# ACS_sch.net
KiCad netlist of a schematic drawn in Altium Designer
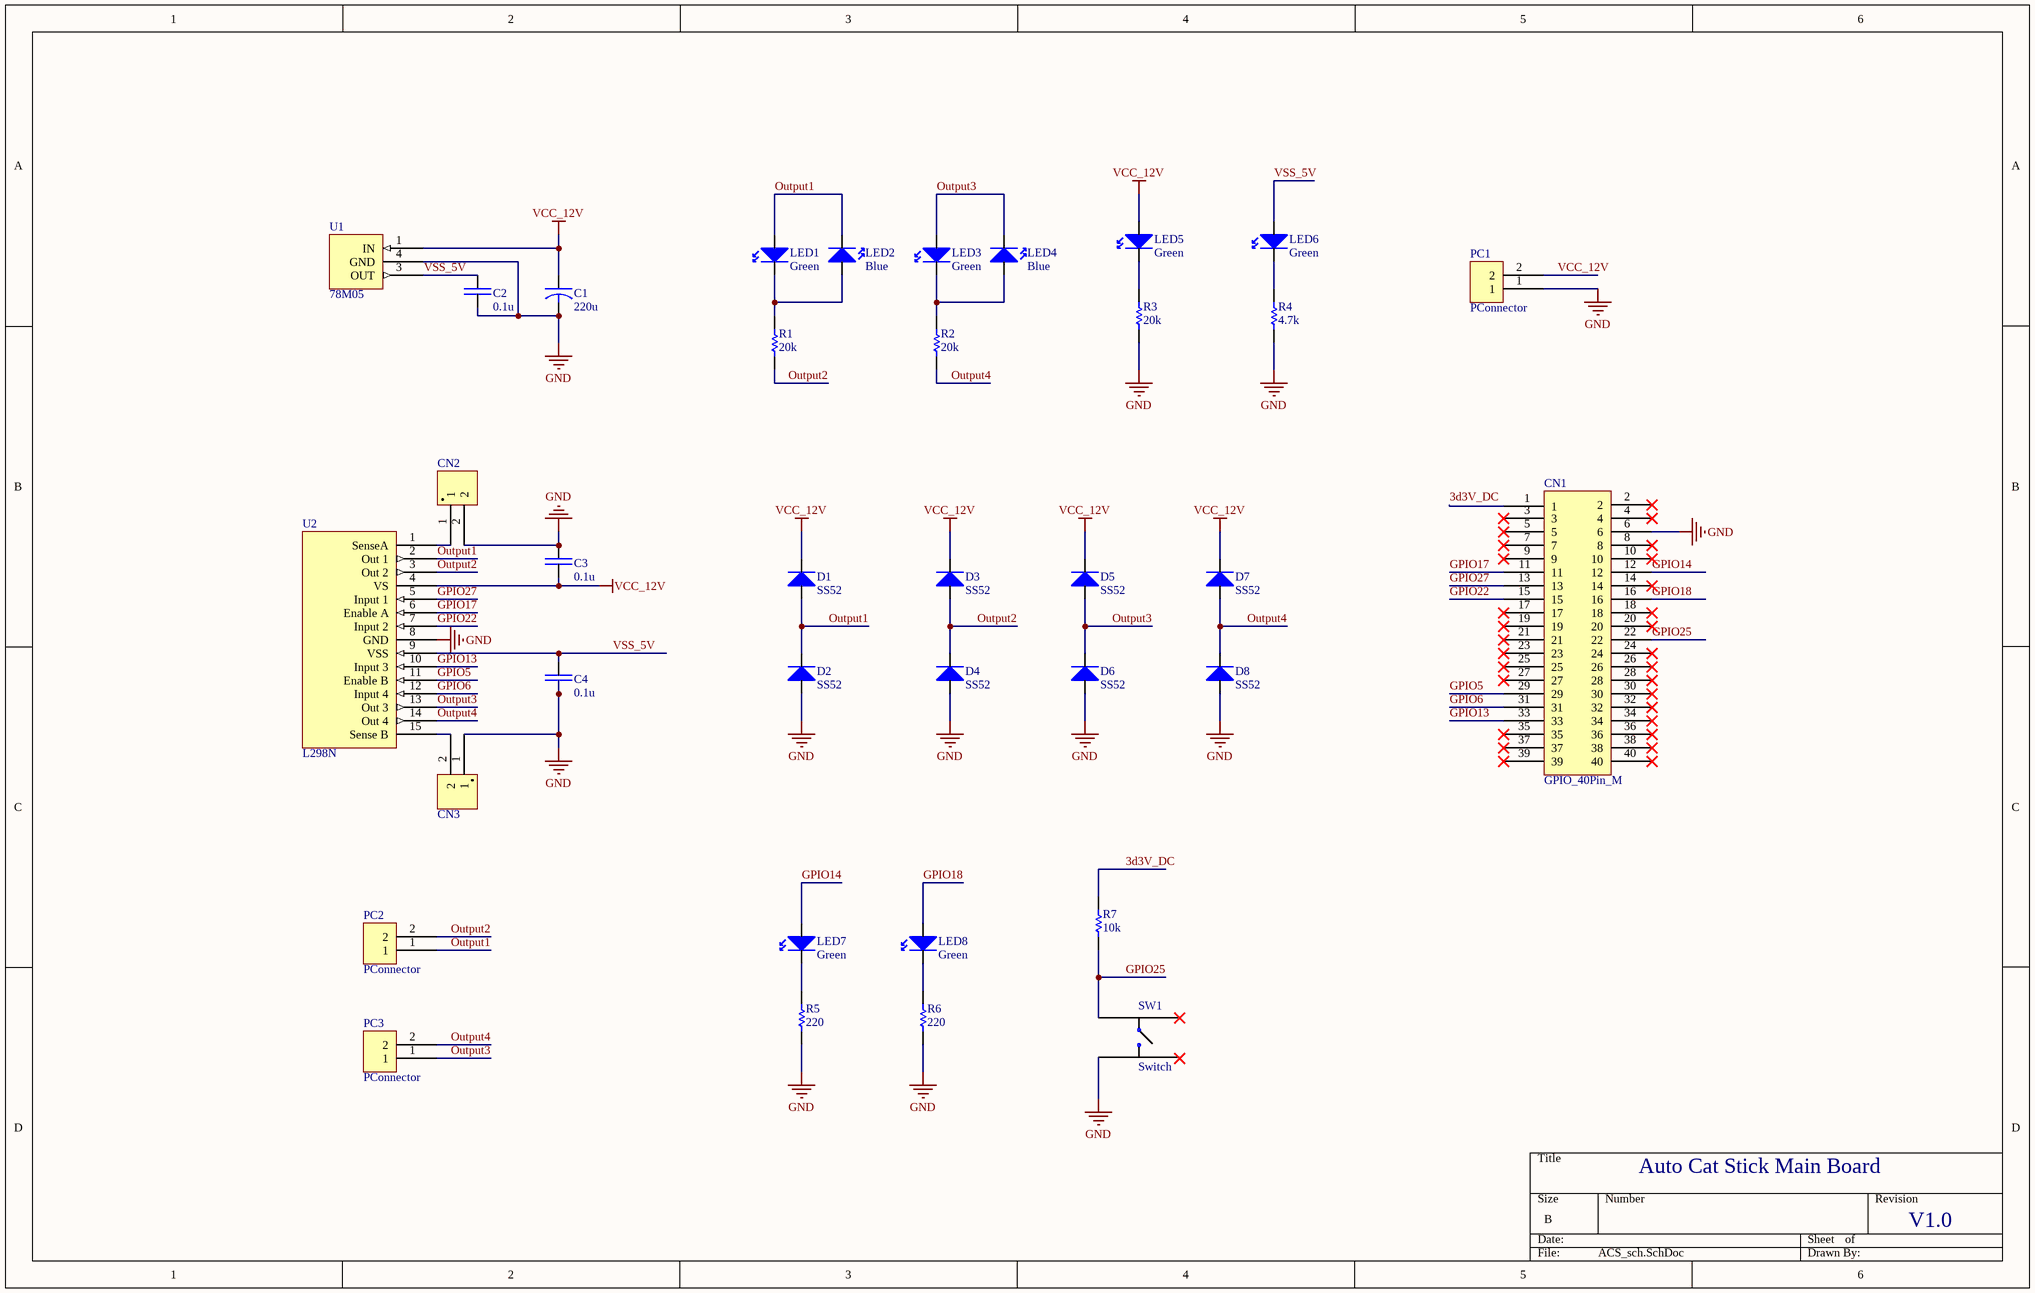
[diagram p0: ACS_sch.SchDoc]

(export (version "E")
  (design (tool "Eeschema 10.0.6"))
  (components
    (comp (ref "C1")
      (value "220u")
      (footprint "C0605")
      (description "C0605 Electrolytic Capacitor")
      (libsource (lib "ACS_SchLib") (part "cap 0605"))
    )
    (comp (ref "C2")
      (value "0.1u")
      (footprint "C0603")
      (description "C0603 non Electrolytic Capacitor")
      (libsource (lib "ACS_SchLib") (part "cap 0603 NonE"))
    )
    (comp (ref "C3")
      (value "0.1u")
      (footprint "C0603")
      (description "C0603 non Electrolytic Capacitor")
      (libsource (lib "ACS_SchLib") (part "cap 0603 NonE"))
    )
    (comp (ref "C4")
      (value "0.1u")
      (footprint "C0603")
      (description "C0603 non Electrolytic Capacitor")
      (libsource (lib "ACS_SchLib") (part "cap 0603 NonE"))
    )
    (comp (ref "CN1")
      (value "GPIO_40Pin_M")
      (footprint "GPIO_40Pin_M")
      (description "GPIO 40pin Male Connector")
      (libsource (lib "ACS_SchLib") (part "GPIO_40Pin_M"))
    )
    (comp (ref "CN2")
      (value "Connector")
      (footprint "2PIN")
      (description "2pin connector")
      (libsource (lib "ACS_SchLib") (part "Connector"))
    )
    (comp (ref "CN3")
      (value "Connector")
      (footprint "2PIN")
      (description "2pin connector")
      (libsource (lib "") (part "Connector_1"))
    )
    (comp (ref "D1")
      (value "SS52")
      (footprint "SMC(DO-214AB)")
      (description "SS52 Diode")
      (libsource (lib "ACS_SchLib") (part "SS52"))
    )
    (comp (ref "D2")
      (value "SS52")
      (footprint "SMC(DO-214AB)")
      (description "SS52 Diode")
      (libsource (lib "ACS_SchLib") (part "SS52"))
    )
    (comp (ref "D3")
      (value "SS52")
      (footprint "SMC(DO-214AB)")
      (description "SS52 Diode")
      (libsource (lib "ACS_SchLib") (part "SS52"))
    )
    (comp (ref "D4")
      (value "SS52")
      (footprint "SMC(DO-214AB)")
      (description "SS52 Diode")
      (libsource (lib "ACS_SchLib") (part "SS52"))
    )
    (comp (ref "D5")
      (value "SS52")
      (footprint "SMC(DO-214AB)")
      (description "SS52 Diode")
      (libsource (lib "ACS_SchLib") (part "SS52"))
    )
    (comp (ref "D6")
      (value "SS52")
      (footprint "SMC(DO-214AB)")
      (description "SS52 Diode")
      (libsource (lib "ACS_SchLib") (part "SS52"))
    )
    (comp (ref "D7")
      (value "SS52")
      (footprint "SMC(DO-214AB)")
      (description "SS52 Diode")
      (libsource (lib "ACS_SchLib") (part "SS52"))
    )
    (comp (ref "D8")
      (value "SS52")
      (footprint "SMC(DO-214AB)")
      (description "SS52 Diode")
      (libsource (lib "ACS_SchLib") (part "SS52"))
    )
    (comp (ref "LED1")
      (value "Green")
      (footprint "LED0603")
      (description "LED0603")
      (libsource (lib "ACS_SchLib") (part "led 0603"))
    )
    (comp (ref "LED2")
      (value "Blue")
      (footprint "LED0603")
      (description "LED0603")
      (libsource (lib "ACS_SchLib") (part "led 0603"))
    )
    (comp (ref "LED3")
      (value "Green")
      (footprint "LED0603")
      (description "LED0603")
      (libsource (lib "ACS_SchLib") (part "led 0603"))
    )
    (comp (ref "LED4")
      (value "Blue")
      (footprint "LED0603")
      (description "LED0603")
      (libsource (lib "ACS_SchLib") (part "led 0603"))
    )
    (comp (ref "LED5")
      (value "Green")
      (footprint "LED0603")
      (description "LED0603")
      (libsource (lib "ACS_SchLib") (part "led 0603"))
    )
    (comp (ref "LED6")
      (value "Green")
      (footprint "LED0603")
      (description "LED0603")
      (libsource (lib "ACS_SchLib") (part "led 0603"))
    )
    (comp (ref "LED7")
      (value "Green")
      (footprint "LED0603")
      (description "LED0603")
      (libsource (lib "ACS_SchLib") (part "led 0603"))
    )
    (comp (ref "LED8")
      (value "Green")
      (footprint "LED0603")
      (description "LED0603")
      (libsource (lib "ACS_SchLib") (part "led 0603"))
    )
    (comp (ref "PC1")
      (value "PConnector")
      (footprint "PC_2Pin")
      (description "2Pin")
      (libsource (lib "ACS_SchLib") (part "PConnector"))
    )
    (comp (ref "PC2")
      (value "PConnector")
      (footprint "PC_2Pin")
      (description "2Pin")
      (libsource (lib "ACS_SchLib") (part "PConnector"))
    )
    (comp (ref "PC3")
      (value "PConnector")
      (footprint "PC_2Pin")
      (description "2Pin")
      (libsource (lib "ACS_SchLib") (part "PConnector"))
    )
    (comp (ref "R1")
      (value "20k")
      (footprint "R0603")
      (description "Resistor")
      (libsource (lib "ACS_SchLib") (part "Res 0603"))
    )
    (comp (ref "R2")
      (value "20k")
      (footprint "R0603")
      (description "Resistor")
      (libsource (lib "ACS_SchLib") (part "Res 0603"))
    )
    (comp (ref "R3")
      (value "20k")
      (footprint "R0603")
      (description "Resistor")
      (libsource (lib "ACS_SchLib") (part "Res 0603"))
    )
    (comp (ref "R4")
      (value "4.7k")
      (footprint "R0603")
      (description "Resistor")
      (libsource (lib "ACS_SchLib") (part "Res 0603"))
    )
    (comp (ref "R5")
      (value "220")
      (footprint "R0603")
      (description "Resistor")
      (libsource (lib "ACS_SchLib") (part "Res 0603"))
    )
    (comp (ref "R6")
      (value "220")
      (footprint "R0603")
      (description "Resistor")
      (libsource (lib "ACS_SchLib") (part "Res 0603"))
    )
    (comp (ref "R7")
      (value "10k")
      (footprint "R0603")
      (description "Resistor")
      (libsource (lib "ACS_SchLib") (part "Res 0603"))
    )
    (comp (ref "SW1") (value "Switch") (footprint "Switch") (libsource (lib "ACS_SchLib") (part "Switch")))
    (comp (ref "U1")
      (value "78M05")
      (footprint "78M05")
      (description "Linear Voltage Regulators (LDO)")
      (libsource (lib "ACS_SchLib") (part "78M05"))
    )
    (comp (ref "U2")
      (value "L298N")
      (footprint "L298N")
      (description "HGSEMI L298N")
      (libsource (lib "ACS_SchLib") (part "L298N"))
    )
  )
  (nets
    (net (code "1") (name "/3d3V_DC") (class "Default")
      (node (ref "CN1") (pin "1") (pinfunction "1_1") (pintype "passive"))
      (node (ref "R7") (pin "2") (pinfunction "2_2") (pintype "passive"))
    )
    (net (code "3") (name "/GPIO5") (class "Default")
      (node (ref "CN1") (pin "29") (pinfunction "29_29") (pintype "passive"))
      (node (ref "U2") (pin "11") (pinfunction "Enable_B_11") (pintype "input"))
    )
    (net (code "4") (name "/GPIO6") (class "Default")
      (node (ref "CN1") (pin "31") (pinfunction "31_31") (pintype "passive"))
      (node (ref "U2") (pin "12") (pinfunction "Input_4_12") (pintype "input"))
    )
    (net (code "5") (name "/GPIO13") (class "Default")
      (node (ref "CN1") (pin "33") (pinfunction "33_33") (pintype "passive"))
      (node (ref "U2") (pin "10") (pinfunction "Input_3_10") (pintype "input"))
    )
    (net (code "6") (name "/GPIO14") (class "Default")
      (node (ref "CN1") (pin "12") (pinfunction "12_12") (pintype "passive"))
      (node (ref "LED7") (pin "2") (pinfunction "2_2") (pintype "passive"))
    )
    (net (code "7") (name "/GPIO17") (class "Default")
      (node (ref "CN1") (pin "11") (pinfunction "11_11") (pintype "passive"))
      (node (ref "U2") (pin "6") (pinfunction "Enable_A_6") (pintype "input"))
    )
    (net (code "8") (name "/GPIO18") (class "Default")
      (node (ref "CN1") (pin "16") (pinfunction "16_16") (pintype "passive"))
      (node (ref "LED8") (pin "2") (pinfunction "2_2") (pintype "passive"))
    )
    (net (code "9") (name "/GPIO22") (class "Default")
      (node (ref "CN1") (pin "15") (pinfunction "15_15") (pintype "passive"))
      (node (ref "U2") (pin "7") (pinfunction "Input_2_7") (pintype "input"))
    )
    (net (code "10") (name "/GPIO25") (class "Default")
      (node (ref "CN1") (pin "22") (pinfunction "22_22") (pintype "passive"))
      (node (ref "R7") (pin "1") (pinfunction "1_1") (pintype "passive"))
      (node (ref "SW1") (pin "1") (pinfunction "1_1") (pintype "passive"))
    )
    (net (code "11") (name "/GPIO27") (class "Default")
      (node (ref "CN1") (pin "13") (pinfunction "13_13") (pintype "passive"))
      (node (ref "U2") (pin "5") (pinfunction "Input_1_5") (pintype "input"))
    )
    (net (code "12") (name "/Output1") (class "Default")
      (node (ref "D1") (pin "2") (pinfunction "2_2") (pintype "passive"))
      (node (ref "D2") (pin "1") (pinfunction "1_1") (pintype "passive"))
      (node (ref "LED1") (pin "2") (pinfunction "2_2") (pintype "passive"))
      (node (ref "LED2") (pin "1") (pinfunction "1_1") (pintype "passive"))
      (node (ref "PC2") (pin "1") (pinfunction "1_1") (pintype "passive"))
      (node (ref "U2") (pin "2") (pinfunction "Out_1_2") (pintype "output"))
    )
    (net (code "13") (name "/Output2") (class "Default")
      (node (ref "D3") (pin "2") (pinfunction "2_2") (pintype "passive"))
      (node (ref "D4") (pin "1") (pinfunction "1_1") (pintype "passive"))
      (node (ref "PC2") (pin "2") (pinfunction "2_2") (pintype "passive"))
      (node (ref "R1") (pin "1") (pinfunction "1_1") (pintype "passive"))
      (node (ref "U2") (pin "3") (pinfunction "Out_2_3") (pintype "output"))
    )
    (net (code "14") (name "/Output3") (class "Default")
      (node (ref "D5") (pin "2") (pinfunction "2_2") (pintype "passive"))
      (node (ref "D6") (pin "1") (pinfunction "1_1") (pintype "passive"))
      (node (ref "LED3") (pin "2") (pinfunction "2_2") (pintype "passive"))
      (node (ref "LED4") (pin "1") (pinfunction "1_1") (pintype "passive"))
      (node (ref "PC3") (pin "1") (pinfunction "1_1") (pintype "passive"))
      (node (ref "U2") (pin "13") (pinfunction "Out_3_13") (pintype "output"))
    )
    (net (code "15") (name "/Output4") (class "Default")
      (node (ref "D7") (pin "2") (pinfunction "2_2") (pintype "passive"))
      (node (ref "D8") (pin "1") (pinfunction "1_1") (pintype "passive"))
      (node (ref "PC3") (pin "2") (pinfunction "2_2") (pintype "passive"))
      (node (ref "R2") (pin "1") (pinfunction "1_1") (pintype "passive"))
      (node (ref "U2") (pin "14") (pinfunction "Out_4_14") (pintype "output"))
    )
    (net (code "16") (name "/VSS_5V") (class "Default")
      (node (ref "C2") (pin "1") (pinfunction "1_1") (pintype "passive"))
      (node (ref "C4") (pin "2") (pinfunction "2_2") (pintype "passive"))
      (node (ref "LED6") (pin "2") (pinfunction "2_2") (pintype "passive"))
      (node (ref "U1") (pin "3") (pinfunction "OUT_3") (pintype "output"))
      (node (ref "U2") (pin "9") (pinfunction "VSS_9") (pintype "input"))
    )
    (net (code "17") (name "GND") (class "Default")
      (node (ref "C1") (pin "2") (pinfunction "2_2") (pintype "passive"))
      (node (ref "C2") (pin "2") (pinfunction "2_2") (pintype "passive"))
      (node (ref "C3") (pin "1") (pinfunction "1_1") (pintype "passive"))
      (node (ref "C4") (pin "1") (pinfunction "1_1") (pintype "passive"))
      (node (ref "CN1") (pin "6") (pinfunction "6_6") (pintype "passive"))
      (node (ref "CN2") (pin "2") (pinfunction "2_2") (pintype "passive"))
      (node (ref "CN3") (pin "1") (pinfunction "1_1") (pintype "passive"))
      (node (ref "D2") (pin "2") (pinfunction "2_2") (pintype "passive"))
      (node (ref "D4") (pin "2") (pinfunction "2_2") (pintype "passive"))
      (node (ref "D6") (pin "2") (pinfunction "2_2") (pintype "passive"))
      (node (ref "D8") (pin "2") (pinfunction "2_2") (pintype "passive"))
      (node (ref "PC1") (pin "1") (pinfunction "1_1") (pintype "passive"))
      (node (ref "R3") (pin "1") (pinfunction "1_1") (pintype "passive"))
      (node (ref "R4") (pin "1") (pinfunction "1_1") (pintype "passive"))
      (node (ref "R5") (pin "1") (pinfunction "1_1") (pintype "passive"))
      (node (ref "R6") (pin "1") (pinfunction "1_1") (pintype "passive"))
      (node (ref "SW1") (pin "3") (pinfunction "3_3") (pintype "passive"))
      (node (ref "U1") (pin "4") (pinfunction "GND_4") (pintype "power_in"))
      (node (ref "U2") (pin "8") (pinfunction "GND_8") (pintype "power_in"))
    )
    (net (code "18") (name "Net-(LED1-Pad1)") (class "Default")
      (node (ref "LED1") (pin "1") (pinfunction "1_1") (pintype "passive"))
      (node (ref "LED2") (pin "2") (pinfunction "2_2") (pintype "passive"))
      (node (ref "R1") (pin "2") (pinfunction "2_2") (pintype "passive"))
    )
    (net (code "19") (name "Net-(LED3-Pad1)") (class "Default")
      (node (ref "LED3") (pin "1") (pinfunction "1_1") (pintype "passive"))
      (node (ref "LED4") (pin "2") (pinfunction "2_2") (pintype "passive"))
      (node (ref "R2") (pin "2") (pinfunction "2_2") (pintype "passive"))
    )
    (net (code "20") (name "Net-(LED5-Pad1)") (class "Default")
      (node (ref "LED5") (pin "1") (pinfunction "1_1") (pintype "passive"))
      (node (ref "R3") (pin "2") (pinfunction "2_2") (pintype "passive"))
    )
    (net (code "21") (name "Net-(LED6-Pad1)") (class "Default")
      (node (ref "LED6") (pin "1") (pinfunction "1_1") (pintype "passive"))
      (node (ref "R4") (pin "2") (pinfunction "2_2") (pintype "passive"))
    )
    (net (code "22") (name "Net-(LED7-Pad1)") (class "Default")
      (node (ref "LED7") (pin "1") (pinfunction "1_1") (pintype "passive"))
      (node (ref "R5") (pin "2") (pinfunction "2_2") (pintype "passive"))
    )
    (net (code "23") (name "Net-(LED8-Pad1)") (class "Default")
      (node (ref "LED8") (pin "1") (pinfunction "1_1") (pintype "passive"))
      (node (ref "R6") (pin "2") (pinfunction "2_2") (pintype "passive"))
    )
    (net (code "24") (name "Net-(U2-SenseA)") (class "Default")
      (node (ref "CN2") (pin "1") (pinfunction "1_1") (pintype "passive"))
      (node (ref "U2") (pin "1") (pinfunction "SenseA_1") (pintype "passive"))
    )
    (net (code "25") (name "Net-(U2-Sense_B)") (class "Default")
      (node (ref "CN3") (pin "2") (pinfunction "2_2") (pintype "passive"))
      (node (ref "U2") (pin "15") (pinfunction "Sense_B_15") (pintype "passive"))
    )
    (net (code "26") (name "VCC_12V") (class "Default")
      (node (ref "C1") (pin "1") (pinfunction "1_1") (pintype "passive"))
      (node (ref "C3") (pin "2") (pinfunction "2_2") (pintype "passive"))
      (node (ref "D1") (pin "1") (pinfunction "1_1") (pintype "passive"))
      (node (ref "D3") (pin "1") (pinfunction "1_1") (pintype "passive"))
      (node (ref "D5") (pin "1") (pinfunction "1_1") (pintype "passive"))
      (node (ref "D7") (pin "1") (pinfunction "1_1") (pintype "passive"))
      (node (ref "LED5") (pin "2") (pinfunction "2_2") (pintype "passive"))
      (node (ref "PC1") (pin "2") (pinfunction "2_2") (pintype "passive"))
      (node (ref "U1") (pin "1") (pinfunction "IN_1") (pintype "input"))
      (node (ref "U2") (pin "4") (pinfunction "VS_4") (pintype "power_in"))
    )
    (net (code "27") (name "unconnected-(CN1-Pad2)") (class "Default")
      (node (ref "CN1") (pin "2") (pinfunction "2_2") (pintype "passive+no_connect"))
    )
    (net (code "28") (name "unconnected-(CN1-Pad3)") (class "Default")
      (node (ref "CN1") (pin "3") (pinfunction "3_3") (pintype "passive+no_connect"))
    )
    (net (code "29") (name "unconnected-(CN1-Pad4)") (class "Default")
      (node (ref "CN1") (pin "4") (pinfunction "4_4") (pintype "passive+no_connect"))
    )
    (net (code "30") (name "unconnected-(CN1-Pad5)") (class "Default")
      (node (ref "CN1") (pin "5") (pinfunction "5_5") (pintype "passive+no_connect"))
    )
    (net (code "31") (name "unconnected-(CN1-Pad7)") (class "Default")
      (node (ref "CN1") (pin "7") (pinfunction "7_7") (pintype "passive+no_connect"))
    )
    (net (code "32") (name "unconnected-(CN1-Pad8)") (class "Default")
      (node (ref "CN1") (pin "8") (pinfunction "8_8") (pintype "passive+no_connect"))
    )
    (net (code "33") (name "unconnected-(CN1-Pad9)") (class "Default")
      (node (ref "CN1") (pin "9") (pinfunction "9_9") (pintype "passive+no_connect"))
    )
    (net (code "34") (name "unconnected-(CN1-Pad10)") (class "Default")
      (node (ref "CN1") (pin "10") (pinfunction "10_10") (pintype "passive+no_connect"))
    )
    (net (code "35") (name "unconnected-(CN1-Pad14)") (class "Default")
      (node (ref "CN1") (pin "14") (pinfunction "14_14") (pintype "passive+no_connect"))
    )
    (net (code "36") (name "unconnected-(CN1-Pad17)") (class "Default")
      (node (ref "CN1") (pin "17") (pinfunction "17_17") (pintype "passive+no_connect"))
    )
    (net (code "37") (name "unconnected-(CN1-Pad18)") (class "Default")
      (node (ref "CN1") (pin "18") (pinfunction "18_18") (pintype "passive+no_connect"))
    )
    (net (code "38") (name "unconnected-(CN1-Pad19)") (class "Default")
      (node (ref "CN1") (pin "19") (pinfunction "19_19") (pintype "passive+no_connect"))
    )
    (net (code "39") (name "unconnected-(CN1-Pad20)") (class "Default")
      (node (ref "CN1") (pin "20") (pinfunction "20_20") (pintype "passive+no_connect"))
    )
    (net (code "40") (name "unconnected-(CN1-Pad21)") (class "Default")
      (node (ref "CN1") (pin "21") (pinfunction "21_21") (pintype "passive+no_connect"))
    )
    (net (code "41") (name "unconnected-(CN1-Pad23)") (class "Default")
      (node (ref "CN1") (pin "23") (pinfunction "23_23") (pintype "passive+no_connect"))
    )
    (net (code "42") (name "unconnected-(CN1-Pad24)") (class "Default")
      (node (ref "CN1") (pin "24") (pinfunction "24_24") (pintype "passive+no_connect"))
    )
    (net (code "43") (name "unconnected-(CN1-Pad25)") (class "Default")
      (node (ref "CN1") (pin "25") (pinfunction "25_25") (pintype "passive+no_connect"))
    )
    (net (code "44") (name "unconnected-(CN1-Pad26)") (class "Default")
      (node (ref "CN1") (pin "26") (pinfunction "26_26") (pintype "passive+no_connect"))
    )
    (net (code "45") (name "unconnected-(CN1-Pad27)") (class "Default")
      (node (ref "CN1") (pin "27") (pinfunction "27_27") (pintype "passive+no_connect"))
    )
    (net (code "46") (name "unconnected-(CN1-Pad28)") (class "Default")
      (node (ref "CN1") (pin "28") (pinfunction "28_28") (pintype "passive+no_connect"))
    )
    (net (code "47") (name "unconnected-(CN1-Pad30)") (class "Default")
      (node (ref "CN1") (pin "30") (pinfunction "30_30") (pintype "passive+no_connect"))
    )
    (net (code "48") (name "unconnected-(CN1-Pad32)") (class "Default")
      (node (ref "CN1") (pin "32") (pinfunction "32_32") (pintype "passive+no_connect"))
    )
    (net (code "49") (name "unconnected-(CN1-Pad34)") (class "Default")
      (node (ref "CN1") (pin "34") (pinfunction "34_34") (pintype "passive+no_connect"))
    )
    (net (code "50") (name "unconnected-(CN1-Pad35)") (class "Default")
      (node (ref "CN1") (pin "35") (pinfunction "35_35") (pintype "passive+no_connect"))
    )
    (net (code "51") (name "unconnected-(CN1-Pad36)") (class "Default")
      (node (ref "CN1") (pin "36") (pinfunction "36_36") (pintype "passive+no_connect"))
    )
    (net (code "52") (name "unconnected-(CN1-Pad37)") (class "Default")
      (node (ref "CN1") (pin "37") (pinfunction "37_37") (pintype "passive+no_connect"))
    )
    (net (code "53") (name "unconnected-(CN1-Pad38)") (class "Default")
      (node (ref "CN1") (pin "38") (pinfunction "38_38") (pintype "passive+no_connect"))
    )
    (net (code "54") (name "unconnected-(CN1-Pad39)") (class "Default")
      (node (ref "CN1") (pin "39") (pinfunction "39_39") (pintype "passive+no_connect"))
    )
    (net (code "55") (name "unconnected-(CN1-Pad40)") (class "Default")
      (node (ref "CN1") (pin "40") (pinfunction "40_40") (pintype "passive+no_connect"))
    )
    (net (code "56") (name "unconnected-(SW1-Pad2)") (class "Default")
      (node (ref "SW1") (pin "2") (pinfunction "2_2") (pintype "passive+no_connect"))
    )
    (net (code "57") (name "unconnected-(SW1-Pad4)") (class "Default")
      (node (ref "SW1") (pin "4") (pinfunction "4_4") (pintype "passive"))
    )
  )
)
